# SolderingIronDriver-V1_5-PTH.net
KiCad netlist of a schematic drawn in EAGLE
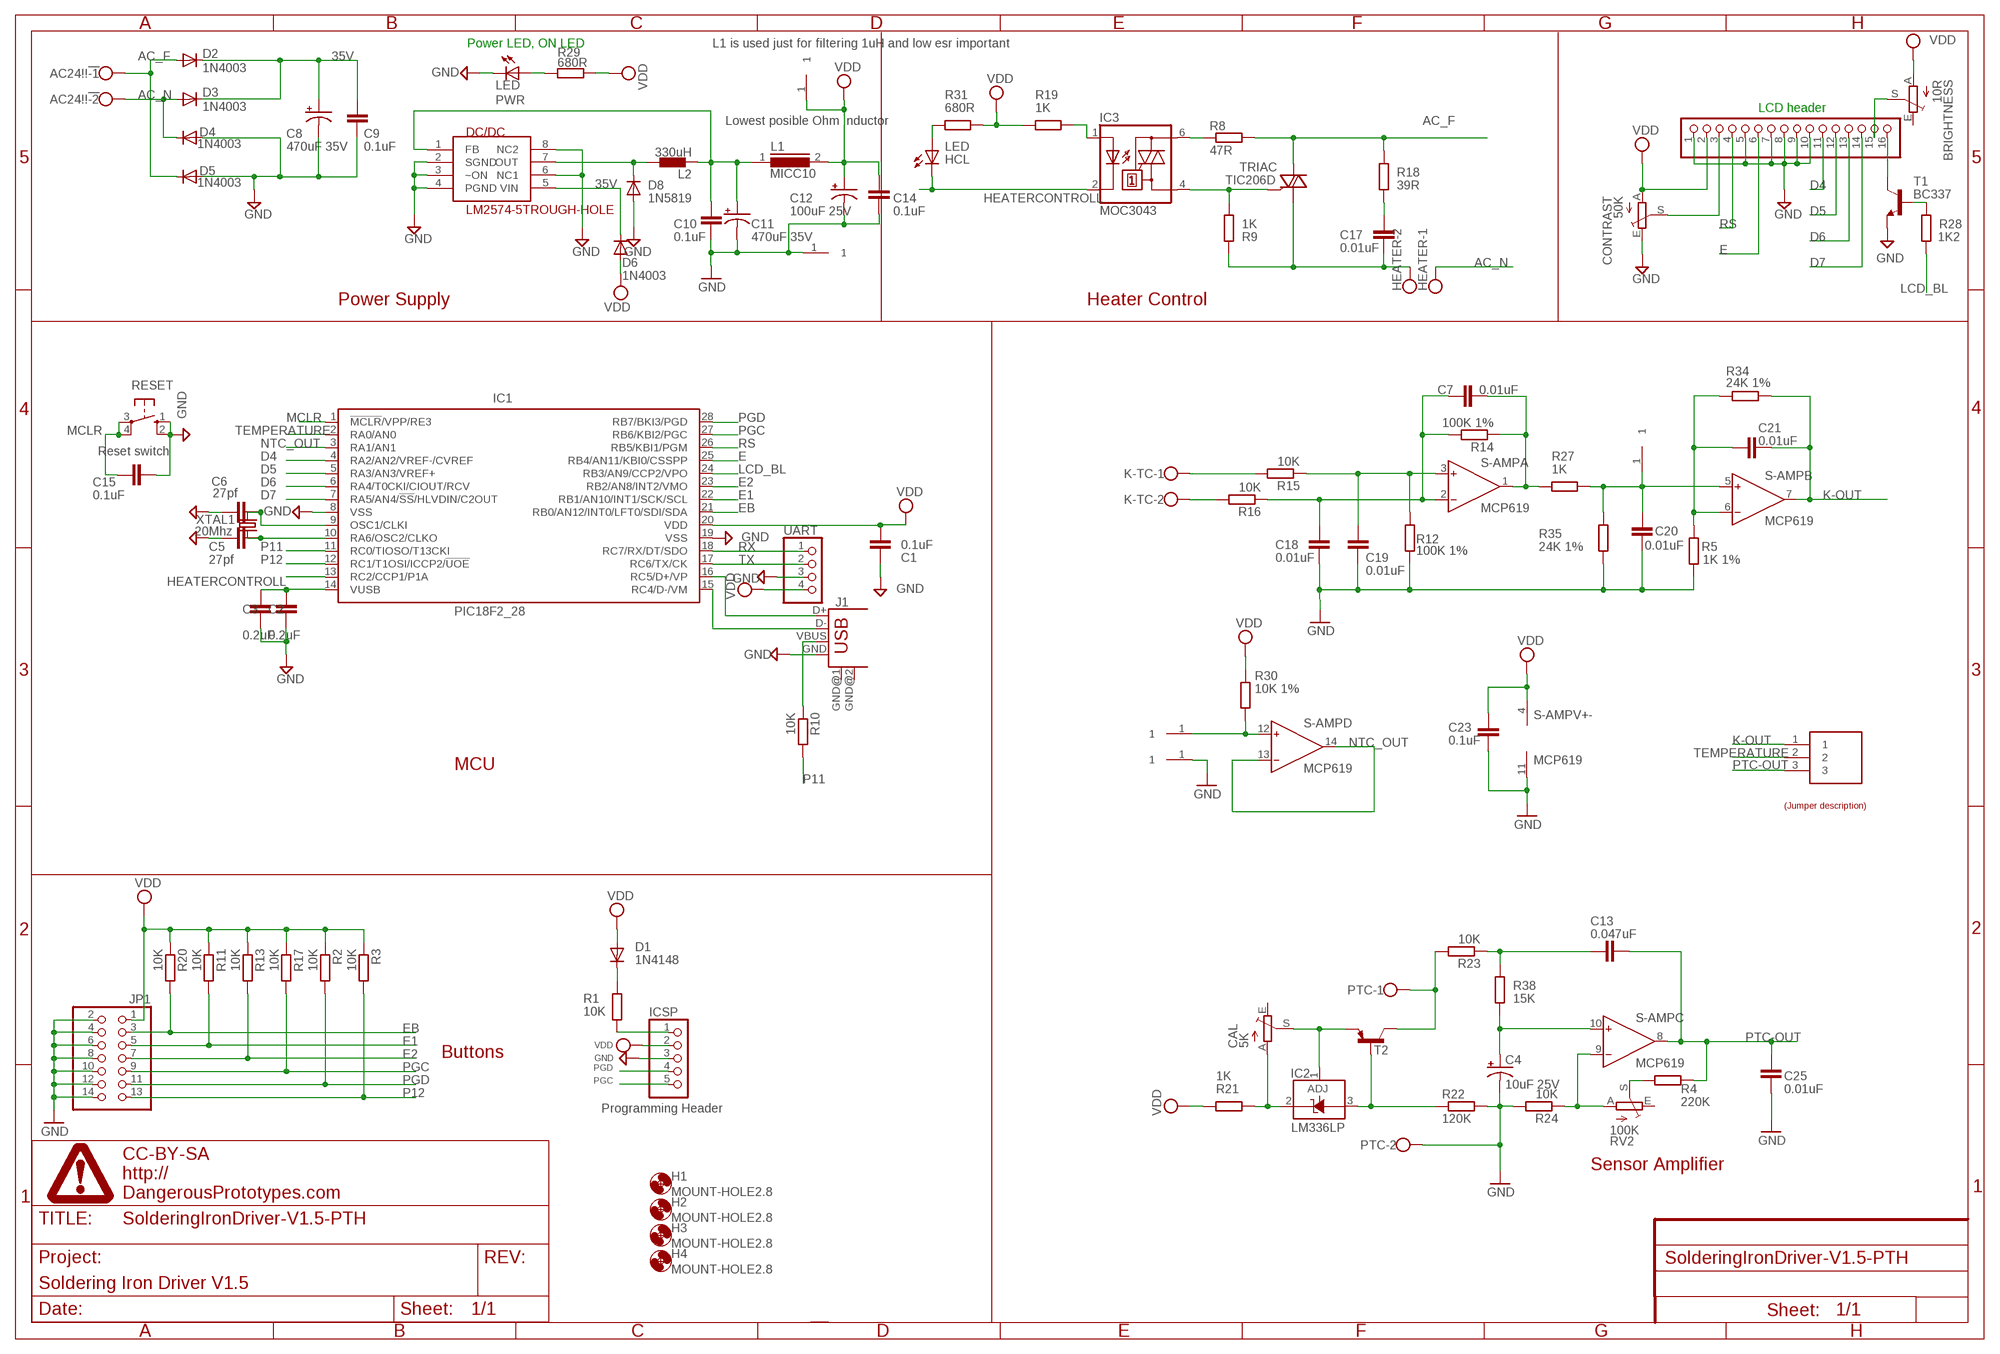
[diagram p0: schematic, sheet 1]

(export (version "E")
  (design (tool "Eeschema 10.0.6"))
  (components
    (comp (ref "5V")
      (value "HEADER1X1PTH")
      (footprint "eagle-import:M1X1")
      (libsource (lib "eagle-import") (part "HEADER1X1PTH"))
    )
    (comp (ref "AC24!!!")
      (value "W237-102")
      (footprint "eagle-import:W237-102")
      (fields (field (name "MPN") "237-102"))
      (libsource (lib "eagle-import") (part "W237-102"))
    )
    (comp (ref "AMP")
      (value "HEADER1X1PTH")
      (footprint "eagle-import:M1X1")
      (libsource (lib "eagle-import") (part "HEADER1X1PTH"))
    )
    (comp (ref "BRIGHTNESS")
      (value "10R")
      (footprint "eagle-import:B25P")
      (libsource (lib "eagle-import") (part "pot_TRIM_EU-B25P"))
    )
    (comp (ref "C1")
      (value "0.1uF")
      (footprint "eagle-import:DEC")
      (libsource (lib "eagle-import") (part "CAPDECOUPLING"))
    )
    (comp (ref "C2")
      (value "0.2uF")
      (footprint "eagle-import:DEC")
      (libsource (lib "eagle-import") (part "CAPDECOUPLING"))
    )
    (comp (ref "C3")
      (value "0.2uF")
      (footprint "eagle-import:DEC")
      (libsource (lib "eagle-import") (part "CAPDECOUPLING"))
    )
    (comp (ref "C4")
      (value "10uF 25V")
      (footprint "eagle-import:CPOL-RADIAL-10UF-25V")
      (libsource (lib "eagle-import") (part "CAP_POLPTH2"))
    )
    (comp (ref "C5")
      (value "27pf")
      (footprint "eagle-import:DEC")
      (libsource (lib "eagle-import") (part "CAPDECOUPLING"))
    )
    (comp (ref "C6")
      (value "27pf")
      (footprint "eagle-import:DEC")
      (libsource (lib "eagle-import") (part "CAPDECOUPLING"))
    )
    (comp (ref "C7")
      (value "0.01uF")
      (footprint "eagle-import:DEC")
      (libsource (lib "eagle-import") (part "CAPDECOUPLING"))
    )
    (comp (ref "C8")
      (value "470uF 35V")
      (footprint "eagle-import:CAP-D10-P200MIL")
      (libsource (lib "eagle-import") (part "CAP-ELD10-P200"))
    )
    (comp (ref "C9")
      (value "0.1uF")
      (footprint "eagle-import:DEC")
      (libsource (lib "eagle-import") (part "CAPDECOUPLING"))
    )
    (comp (ref "C10")
      (value "0.1uF")
      (footprint "eagle-import:DEC")
      (libsource (lib "eagle-import") (part "CAPDECOUPLING"))
    )
    (comp (ref "C11")
      (value "470uF 35V")
      (footprint "eagle-import:CAP-D6.3MM-P100MIL")
      (libsource (lib "eagle-import") (part "CAP-ELD63MP100"))
    )
    (comp (ref "C12")
      (value "100uF 25V")
      (footprint "eagle-import:CPOL-RADIAL-100UF-25V")
      (libsource (lib "eagle-import") (part "CAP_POLPTH1"))
    )
    (comp (ref "C13")
      (value "0.047uF")
      (footprint "eagle-import:DEC")
      (libsource (lib "eagle-import") (part "CAPDECOUPLING"))
    )
    (comp (ref "C14")
      (value "0.1uF")
      (footprint "eagle-import:DEC")
      (libsource (lib "eagle-import") (part "CAPDECOUPLING"))
    )
    (comp (ref "C15")
      (value "0.1uF")
      (footprint "eagle-import:DEC")
      (libsource (lib "eagle-import") (part "CAPDECOUPLING"))
    )
    (comp (ref "C17")
      (value "0.01uF")
      (footprint "eagle-import:DEC")
      (libsource (lib "eagle-import") (part "CAPDECOUPLING"))
    )
    (comp (ref "C18")
      (value "0.01uF")
      (footprint "eagle-import:DEC")
      (libsource (lib "eagle-import") (part "CAPDECOUPLING"))
    )
    (comp (ref "C19")
      (value "0.01uF")
      (footprint "eagle-import:DEC")
      (libsource (lib "eagle-import") (part "CAPDECOUPLING"))
    )
    (comp (ref "C20")
      (value "0.01uF")
      (footprint "eagle-import:DEC")
      (libsource (lib "eagle-import") (part "CAPDECOUPLING"))
    )
    (comp (ref "C21")
      (value "0.01uF")
      (footprint "eagle-import:DEC")
      (libsource (lib "eagle-import") (part "CAPDECOUPLING"))
    )
    (comp (ref "C23")
      (value "0.1uF")
      (footprint "eagle-import:DEC")
      (libsource (lib "eagle-import") (part "CAPDECOUPLING"))
    )
    (comp (ref "C25")
      (value "0.01uF")
      (footprint "eagle-import:DEC")
      (libsource (lib "eagle-import") (part "CAPDECOUPLING"))
    )
    (comp (ref "CAL")
      (value "5K")
      (footprint "eagle-import:RJ9W")
      (libsource (lib "eagle-import") (part "TRIM_EU-RJ9W"))
    )
    (comp (ref "CONTRAST")
      (value "50K")
      (footprint "eagle-import:B25P")
      (libsource (lib "eagle-import") (part "pot_TRIM_EU-B25P"))
    )
    (comp (ref "D1")
      (value "1N4148")
      (footprint "eagle-import:DO35-7")
      (libsource (lib "eagle-import") (part "1N4148DO35-7"))
    )
    (comp (ref "D2")
      (value "1N4003")
      (footprint "eagle-import:DO41-7.6")
      (libsource (lib "eagle-import") (part "DIODE-DO41-7.6"))
    )
    (comp (ref "D3")
      (value "1N4003")
      (footprint "eagle-import:DO41-7.6")
      (libsource (lib "eagle-import") (part "DIODE-DO41-7.6"))
    )
    (comp (ref "D4")
      (value "1N4003")
      (footprint "eagle-import:DO41-7.6")
      (libsource (lib "eagle-import") (part "DIODE-DO41-7.6"))
    )
    (comp (ref "D5")
      (value "1N4003")
      (footprint "eagle-import:DO41-7.6")
      (libsource (lib "eagle-import") (part "DIODE-DO41-7.6"))
    )
    (comp (ref "D6")
      (value "1N4003")
      (footprint "eagle-import:DO41-7.6")
      (libsource (lib "eagle-import") (part "DIODE-DO41-7.6"))
    )
    (comp (ref "D8")
      (value "1N5819")
      (footprint "eagle-import:DO41-7.6")
      (libsource (lib "eagle-import") (part "DIODE-DO41-7.6"))
    )
    (comp (ref "DC/DC")
      (value "LM2574-5TROUGH-HOLE")
      (footprint "eagle-import:DIL-08")
      (libsource (lib "eagle-import") (part "LM2574-5TROUGH-HOLE"))
    )
    (comp (ref "GND")
      (value "HEADER1X1PTH")
      (footprint "eagle-import:M1X1")
      (libsource (lib "eagle-import") (part "HEADER1X1PTH"))
    )
    (comp (ref "H1")
      (value "MOUNT-HOLE2.8")
      (footprint "eagle-import:2,8")
      (libsource (lib "eagle-import") (part "MOUNT-HOLE2.8"))
    )
    (comp (ref "H2")
      (value "MOUNT-HOLE2.8")
      (footprint "eagle-import:2,8")
      (libsource (lib "eagle-import") (part "MOUNT-HOLE2.8"))
    )
    (comp (ref "H3")
      (value "MOUNT-HOLE2.8")
      (footprint "eagle-import:2,8")
      (libsource (lib "eagle-import") (part "MOUNT-HOLE2.8"))
    )
    (comp (ref "H4")
      (value "MOUNT-HOLE2.8")
      (footprint "eagle-import:2,8")
      (libsource (lib "eagle-import") (part "MOUNT-HOLE2.8"))
    )
    (comp (ref "HCL")
      (value "LED")
      (footprint "eagle-import:LED3MM")
      (libsource (lib "eagle-import") (part "LED3MM"))
    )
    (comp (ref "HEATER")
      (value "W237-102")
      (footprint "eagle-import:W237-102")
      (fields (field (name "MPN") "237-102"))
      (libsource (lib "eagle-import") (part "W237-102"))
    )
    (comp (ref "IC1")
      (value "PIC18F2_28")
      (footprint "eagle-import:SOCKET-28-3")
      (libsource (lib "eagle-import") (part "PIC18F2_28"))
    )
    (comp (ref "IC2")
      (value "LM336LP")
      (footprint "eagle-import:TO92")
      (libsource (lib "eagle-import") (part "LM336LP"))
    )
    (comp (ref "IC3")
      (value "MOC3043")
      (footprint "eagle-import:DIL06")
      (fields (field (name "MF") "FAIRCHILD SEMICONDUCTOR") (field (name "MPN") "MOC3043-M"))
      (libsource (lib "eagle-import") (part "MOC3043M"))
    )
    (comp (ref "ICSP")
      (value "PINHD-1X5")
      (footprint "eagle-import:1X05")
      (libsource (lib "eagle-import") (part "PINHD-1X5"))
    )
    (comp (ref "JP1")
      (value "PINHD-2X7")
      (footprint "eagle-import:2X07")
      (libsource (lib "eagle-import") (part "PINHD-2X7"))
    )
    (comp (ref "K-TC")
      (value "W237-102")
      (footprint "eagle-import:W237-102")
      (fields (field (name "MPN") "237-102"))
      (libsource (lib "eagle-import") (part "W237-102"))
    )
    (comp (ref "L1")
      (value "MICC10")
      (footprint "eagle-import:MICC10")
      (libsource (lib "eagle-import") (part "MICC10"))
    )
    (comp (ref "L2")
      (value "330uH")
      (footprint "eagle-import:CW8A")
      (libsource (lib "eagle-import") (part "CL330UH"))
    )
    (comp (ref "LCD_HEADER")
      (value "PINHD-1X16")
      (footprint "eagle-import:1X16")
      (libsource (lib "eagle-import") (part "PINHD-1X16"))
    )
    (comp (ref "NTC")
      (value "HEADER1X1PTH")
      (footprint "eagle-import:M1X1")
      (libsource (lib "eagle-import") (part "HEADER1X1PTH"))
    )
    (comp (ref "ON/OFF2")
      (value "HEADER1X1PTH")
      (footprint "eagle-import:M1X1")
      (libsource (lib "eagle-import") (part "HEADER1X1PTH"))
    )
    (comp (ref "PTC")
      (value "W237-102")
      (footprint "eagle-import:W237-102")
      (fields (field (name "MPN") "237-102"))
      (libsource (lib "eagle-import") (part "W237-102"))
    )
    (comp (ref "PWR")
      (value "LED")
      (footprint "eagle-import:LED3MM")
      (libsource (lib "eagle-import") (part "LED3MM"))
    )
    (comp (ref "R1")
      (value "10K")
      (footprint "eagle-import:0204_7")
      (libsource (lib "eagle-import") (part "R-EU_0204/7"))
    )
    (comp (ref "R2")
      (value "10K")
      (footprint "eagle-import:RTH025W")
      (libsource (lib "eagle-import") (part "RESISTORTH"))
    )
    (comp (ref "R3")
      (value "10K")
      (footprint "eagle-import:RTH025W")
      (libsource (lib "eagle-import") (part "RESISTORTH"))
    )
    (comp (ref "R4")
      (value "220K")
      (footprint "eagle-import:RTH025W")
      (libsource (lib "eagle-import") (part "RESISTORTH"))
    )
    (comp (ref "R5")
      (value "1K 1%")
      (footprint "eagle-import:RTH025W")
      (libsource (lib "eagle-import") (part "RESISTORTH"))
    )
    (comp (ref "R8")
      (value "47R")
      (footprint "eagle-import:RTH025W")
      (libsource (lib "eagle-import") (part "RESISTORTH"))
    )
    (comp (ref "R9")
      (value "1K")
      (footprint "eagle-import:RTH025W")
      (libsource (lib "eagle-import") (part "RESISTORTH"))
    )
    (comp (ref "R10")
      (value "10K")
      (footprint "eagle-import:RTH025W")
      (libsource (lib "eagle-import") (part "RESISTORTH"))
    )
    (comp (ref "R11")
      (value "10K")
      (footprint "eagle-import:RTH025W")
      (libsource (lib "eagle-import") (part "RESISTORTH"))
    )
    (comp (ref "R12")
      (value "100K 1%")
      (footprint "eagle-import:RTH025W")
      (libsource (lib "eagle-import") (part "RESISTORTH"))
    )
    (comp (ref "R13")
      (value "10K")
      (footprint "eagle-import:RTH025W")
      (libsource (lib "eagle-import") (part "RESISTORTH"))
    )
    (comp (ref "R14")
      (value "100K 1%")
      (footprint "eagle-import:RTH025W")
      (libsource (lib "eagle-import") (part "RESISTORTH"))
    )
    (comp (ref "R15")
      (value "10K")
      (footprint "eagle-import:RTH025W")
      (libsource (lib "eagle-import") (part "RESISTORTH"))
    )
    (comp (ref "R16")
      (value "10K")
      (footprint "eagle-import:RTH025W")
      (libsource (lib "eagle-import") (part "RESISTORTH"))
    )
    (comp (ref "R17")
      (value "10K")
      (footprint "eagle-import:RTH025W")
      (libsource (lib "eagle-import") (part "RESISTORTH"))
    )
    (comp (ref "R18")
      (value "39R")
      (footprint "eagle-import:RTH025W")
      (libsource (lib "eagle-import") (part "RESISTORTH"))
    )
    (comp (ref "R19")
      (value "1K")
      (footprint "eagle-import:RTH025W")
      (libsource (lib "eagle-import") (part "RESISTORTH"))
    )
    (comp (ref "R20")
      (value "10K")
      (footprint "eagle-import:RTH025W")
      (libsource (lib "eagle-import") (part "RESISTORTH"))
    )
    (comp (ref "R21")
      (value "1K")
      (footprint "eagle-import:RTH025W")
      (libsource (lib "eagle-import") (part "RESISTORTH"))
    )
    (comp (ref "R22")
      (value "120K")
      (footprint "eagle-import:RTH025W")
      (libsource (lib "eagle-import") (part "RESISTORTH"))
    )
    (comp (ref "R23")
      (value "10K")
      (footprint "eagle-import:RTH025W")
      (libsource (lib "eagle-import") (part "RESISTORTH"))
    )
    (comp (ref "R24")
      (value "10K")
      (footprint "eagle-import:RTH025W")
      (libsource (lib "eagle-import") (part "RESISTORTH"))
    )
    (comp (ref "R27")
      (value "1K")
      (footprint "eagle-import:RTH025W")
      (libsource (lib "eagle-import") (part "RESISTORTH"))
    )
    (comp (ref "R28")
      (value "1K2")
      (footprint "eagle-import:RTH025W")
      (libsource (lib "eagle-import") (part "RESISTORTH"))
    )
    (comp (ref "R29")
      (value "680R")
      (footprint "eagle-import:RTH025W")
      (libsource (lib "eagle-import") (part "RESISTORTH"))
    )
    (comp (ref "R30")
      (value "10K 1%")
      (footprint "eagle-import:RTH025W")
      (libsource (lib "eagle-import") (part "RESISTORTH"))
    )
    (comp (ref "R31")
      (value "680R")
      (footprint "eagle-import:RTH025W")
      (libsource (lib "eagle-import") (part "RESISTORTH"))
    )
    (comp (ref "R34")
      (value "24K 1%")
      (footprint "eagle-import:RTH025W")
      (libsource (lib "eagle-import") (part "RESISTORTH"))
    )
    (comp (ref "R35")
      (value "24K 1%")
      (footprint "eagle-import:RTH025W")
      (libsource (lib "eagle-import") (part "RESISTORTH"))
    )
    (comp (ref "R38")
      (value "15K")
      (footprint "eagle-import:RTH025W")
      (libsource (lib "eagle-import") (part "RESISTORTH"))
    )
    (comp (ref "RESET")
      (value "10-XX")
      (footprint "eagle-import:B3F-10XX")
      (fields (field (name "MPN") "B3F-1000"))
      (libsource (lib "eagle-import") (part "10-XX"))
    )
    (comp (ref "RV2")
      (value "100K")
      (footprint "eagle-import:RJ9W")
      (libsource (lib "eagle-import") (part "TRIM_EU-RJ9W"))
    )
    (comp (ref "S-AMP")
      (value "MCP619")
      (footprint "eagle-import:SOCKET-14")
      (libsource (lib "eagle-import") (part "MCP619"))
    )
    (comp (ref "SENSOR_SELECT")
      (value "HEADER1X3PTH")
      (footprint "eagle-import:M1X3")
      (libsource (lib "eagle-import") (part "HEADER1X3PTH"))
    )
    (comp (ref "T1")
      (value "BC337")
      (footprint "eagle-import:TO92-CBE")
      (libsource (lib "eagle-import") (part "-NPN-TO92-CBEBC337-40"))
    )
    (comp (ref "T2")
      (value "BJT-PNPTO92EBC")
      (footprint "eagle-import:TO92-EBC")
      (libsource (lib "eagle-import") (part "BJT-PNPTO92EBC"))
    )
    (comp (ref "TRIAC")
      (value "TIC206D")
      (footprint "eagle-import:TO220BV")
      (libsource (lib "eagle-import") (part "TIC206D"))
    )
    (comp (ref "U$1")
      (value "DINA4_L")
      (footprint "eagle-import:DP_LOGO")
      (fields (field (name "PROJECT") "Soldering Iron Driver V1.5"))
      (libsource (lib "eagle-import") (part "DINA4_L"))
    )
    (comp (ref "U$2")
      (value "JUMP3_DESC")
      (footprint "eagle-import:JUMP3_DESC")
      (fields (field (name "LEFT") "PTC") (field (name "RIGHT") "K-TC"))
      (libsource (lib "eagle-import") (part "JUMP3_DESC"))
    )
    (comp (ref "UART")
      (value "PINHD-1X4")
      (footprint "eagle-import:1X04")
      (libsource (lib "eagle-import") (part "PINHD-1X4"))
    )
    (comp (ref "USB")
      (value "USB")
      (footprint "eagle-import:USB-B-H")
      (libsource (lib "eagle-import") (part "USB-B-H"))
    )
    (comp (ref "XTAL1")
      (value "20Mhz")
      (footprint "eagle-import:HC49U70")
      (libsource (lib "eagle-import") (part "CRYSTALHC49U70"))
    )
  )
  (nets
    (net (code "1") (name "/35V") (class "Default")
      (node (ref "C8") (pin "+") (pinfunction "+_+") (pintype "passive"))
      (node (ref "C9") (pin "2") (pinfunction "2_2") (pintype "passive"))
      (node (ref "D2") (pin "C") (pinfunction "C_C") (pintype "passive"))
      (node (ref "D3") (pin "C") (pinfunction "C_C") (pintype "passive"))
      (node (ref "D6") (pin "C") (pinfunction "C_C") (pintype "passive"))
      (node (ref "DC/DC") (pin "5") (pinfunction "VIN_5") (pintype "bidirectional"))
    )
    (net (code "2") (name "/AC_F") (class "Default")
      (node (ref "AC24!!!") (pin "1") (pinfunction "KL_1") (pintype "passive"))
      (node (ref "D2") (pin "A") (pinfunction "A_A") (pintype "passive"))
      (node (ref "D5") (pin "C") (pinfunction "C_C") (pintype "passive"))
      (node (ref "R18") (pin "1") (pinfunction "1_1") (pintype "passive"))
      (node (ref "R8") (pin "2") (pinfunction "2_2") (pintype "passive"))
      (node (ref "TRIAC") (pin "T2") (pinfunction "A2_T2") (pintype "passive"))
    )
    (net (code "3") (name "/AC_N") (class "Default")
      (node (ref "AC24!!!") (pin "2") (pinfunction "KL_2") (pintype "passive"))
      (node (ref "D3") (pin "A") (pinfunction "A_A") (pintype "passive"))
      (node (ref "D4") (pin "C") (pinfunction "C_C") (pintype "passive"))
      (node (ref "HEATER") (pin "1") (pinfunction "KL_1") (pintype "passive"))
    )
    (net (code "4") (name "/D4") (class "Default")
      (node (ref "IC1") (pin "4") (pinfunction "RA2/AN2/VREF-/CVREF_4") (pintype "bidirectional"))
      (node (ref "LCD_HEADER") (pin "11") (pinfunction "11_11") (pintype "passive"))
    )
    (net (code "5") (name "/D5") (class "Default")
      (node (ref "IC1") (pin "5") (pinfunction "RA3/AN3/VREF+_5") (pintype "bidirectional"))
      (node (ref "LCD_HEADER") (pin "12") (pinfunction "12_12") (pintype "passive"))
    )
    (net (code "6") (name "/D6") (class "Default")
      (node (ref "IC1") (pin "6") (pinfunction "RA4/T0CKI/CIOUT/RCV_6") (pintype "bidirectional"))
      (node (ref "LCD_HEADER") (pin "13") (pinfunction "13_13") (pintype "passive"))
    )
    (net (code "7") (name "/D7") (class "Default")
      (node (ref "IC1") (pin "7") (pinfunction "RA5/AN4/~{SS}/HLVDIN/C2OUT_7") (pintype "bidirectional"))
      (node (ref "LCD_HEADER") (pin "14") (pinfunction "14_14") (pintype "passive"))
    )
    (net (code "8") (name "/E") (class "Default")
      (node (ref "IC1") (pin "25") (pinfunction "RB4/AN11/KBI0/CSSPP_25") (pintype "bidirectional"))
      (node (ref "LCD_HEADER") (pin "6") (pinfunction "6_6") (pintype "passive"))
    )
    (net (code "9") (name "/E1") (class "Default")
      (node (ref "IC1") (pin "22") (pinfunction "RB1/AN10/INT1/SCK/SCL_22") (pintype "bidirectional"))
      (node (ref "JP1") (pin "5") (pinfunction "5_5") (pintype "passive"))
      (node (ref "R11") (pin "2") (pinfunction "2_2") (pintype "passive"))
    )
    (net (code "10") (name "/E2") (class "Default")
      (node (ref "IC1") (pin "23") (pinfunction "RB2/AN8/INT2/VMO_23") (pintype "bidirectional"))
      (node (ref "JP1") (pin "7") (pinfunction "7_7") (pintype "passive"))
      (node (ref "R13") (pin "2") (pinfunction "2_2") (pintype "passive"))
    )
    (net (code "11") (name "/EB") (class "Default")
      (node (ref "IC1") (pin "21") (pinfunction "RB0/AN12/INT0/LFT0/SDI/SDA_21") (pintype "bidirectional"))
      (node (ref "JP1") (pin "3") (pinfunction "3_3") (pintype "passive"))
      (node (ref "R20") (pin "2") (pinfunction "2_2") (pintype "passive"))
    )
    (net (code "12") (name "/HEATERCONTROLL") (class "Default")
      (node (ref "HCL") (pin "K") (pinfunction "C_K") (pintype "passive"))
      (node (ref "IC1") (pin "13") (pinfunction "RC2/CCP1/P1A_13") (pintype "bidirectional"))
      (node (ref "IC3") (pin "2") (pinfunction "C_2") (pintype "passive"))
    )
    (net (code "13") (name "/K-OUT") (class "Default")
      (node (ref "C21") (pin "2") (pinfunction "2_2") (pintype "passive"))
      (node (ref "R34") (pin "2") (pinfunction "2_2") (pintype "passive"))
      (node (ref "S-AMP") (pin "7") (pinfunction "OUT_7") (pintype "output"))
      (node (ref "SENSOR_SELECT") (pin "1") (pinfunction "1_1") (pintype "bidirectional"))
    )
    (net (code "14") (name "/LCD_BL") (class "Default")
      (node (ref "IC1") (pin "24") (pinfunction "RB3/AN9/CCP2/VPO_24") (pintype "bidirectional"))
      (node (ref "R28") (pin "2") (pinfunction "2_2") (pintype "passive"))
    )
    (net (code "15") (name "/MCLR") (class "Default")
      (node (ref "C15") (pin "2") (pinfunction "2_2") (pintype "passive"))
      (node (ref "IC1") (pin "1") (pinfunction "~{MCLR}/VPP/RE3_1") (pintype "input"))
      (node (ref "ICSP") (pin "1") (pinfunction "1_1") (pintype "passive"))
      (node (ref "R1") (pin "1") (pinfunction "1_1") (pintype "passive"))
      (node (ref "RESET") (pin "3") (pinfunction "P_3") (pintype "passive"))
      (node (ref "RESET") (pin "4") (pinfunction "P1_4") (pintype "passive"))
    )
    (net (code "16") (name "/NTC_OUT") (class "Default")
      (node (ref "IC1") (pin "3") (pinfunction "RA1/AN1_3") (pintype "bidirectional"))
      (node (ref "S-AMP") (pin "13") (pinfunction "IN-_13") (pintype "input"))
      (node (ref "S-AMP") (pin "14") (pinfunction "OUT_14") (pintype "output"))
    )
    (net (code "17") (name "/P11") (class "Default")
      (node (ref "IC1") (pin "11") (pinfunction "RC0/TIOSO/T13CKI_11") (pintype "bidirectional"))
      (node (ref "R10") (pin "2") (pinfunction "2_2") (pintype "passive"))
    )
    (net (code "18") (name "/P12") (class "Default")
      (node (ref "IC1") (pin "12") (pinfunction "RC1/T1OSI/ICCP2/~{UOE}_12") (pintype "bidirectional"))
      (node (ref "JP1") (pin "13") (pinfunction "13_13") (pintype "passive"))
      (node (ref "R3") (pin "2") (pinfunction "2_2") (pintype "passive"))
    )
    (net (code "19") (name "/PGC") (class "Default")
      (node (ref "IC1") (pin "27") (pinfunction "RB6/KBI2/PGC_27") (pintype "bidirectional"))
      (node (ref "ICSP") (pin "5") (pinfunction "5_5") (pintype "passive"))
      (node (ref "JP1") (pin "9") (pinfunction "9_9") (pintype "passive"))
      (node (ref "R17") (pin "2") (pinfunction "2_2") (pintype "passive"))
    )
    (net (code "20") (name "/PGD") (class "Default")
      (node (ref "IC1") (pin "28") (pinfunction "RB7/BKI3/PGD_28") (pintype "bidirectional"))
      (node (ref "ICSP") (pin "4") (pinfunction "4_4") (pintype "passive"))
      (node (ref "JP1") (pin "11") (pinfunction "11_11") (pintype "passive"))
      (node (ref "R2") (pin "2") (pinfunction "2_2") (pintype "passive"))
    )
    (net (code "21") (name "/PTC-OUT") (class "Default")
      (node (ref "C13") (pin "2") (pinfunction "2_2") (pintype "passive"))
      (node (ref "C25") (pin "2") (pinfunction "2_2") (pintype "passive"))
      (node (ref "R4") (pin "1") (pinfunction "1_1") (pintype "passive"))
      (node (ref "S-AMP") (pin "8") (pinfunction "OUT_8") (pintype "output"))
      (node (ref "SENSOR_SELECT") (pin "3") (pinfunction "3_3") (pintype "bidirectional"))
    )
    (net (code "22") (name "/RS") (class "Default")
      (node (ref "IC1") (pin "26") (pinfunction "RB5/KBI1/PGM_26") (pintype "bidirectional"))
      (node (ref "LCD_HEADER") (pin "4") (pinfunction "4_4") (pintype "passive"))
    )
    (net (code "23") (name "/RX") (class "Default")
      (node (ref "IC1") (pin "18") (pinfunction "RC7/RX/DT/SDO_18") (pintype "bidirectional"))
      (node (ref "UART") (pin "1") (pinfunction "1_1") (pintype "passive"))
    )
    (net (code "24") (name "/TEMPERATURE") (class "Default")
      (node (ref "IC1") (pin "2") (pinfunction "RA0/AN0_2") (pintype "bidirectional"))
      (node (ref "SENSOR_SELECT") (pin "2") (pinfunction "2_2") (pintype "bidirectional"))
    )
    (net (code "25") (name "/TX") (class "Default")
      (node (ref "IC1") (pin "17") (pinfunction "RC6/TX/CK_17") (pintype "bidirectional"))
      (node (ref "UART") (pin "2") (pinfunction "2_2") (pintype "passive"))
    )
    (net (code "26") (name "GND") (class "Default")
      (node (ref "C1") (pin "2") (pinfunction "2_2") (pintype "passive"))
      (node (ref "C10") (pin "1") (pinfunction "1_1") (pintype "passive"))
      (node (ref "C11") (pin "-") (pinfunction "-_-") (pintype "passive"))
      (node (ref "C12") (pin "2") (pinfunction "-_2") (pintype "passive"))
      (node (ref "C14") (pin "1") (pinfunction "1_1") (pintype "passive"))
      (node (ref "C15") (pin "1") (pinfunction "1_1") (pintype "passive"))
      (node (ref "C18") (pin "2") (pinfunction "2_2") (pintype "passive"))
      (node (ref "C19") (pin "2") (pinfunction "2_2") (pintype "passive"))
      (node (ref "C2") (pin "2") (pinfunction "2_2") (pintype "passive"))
      (node (ref "C20") (pin "2") (pinfunction "2_2") (pintype "passive"))
      (node (ref "C23") (pin "1") (pinfunction "1_1") (pintype "passive"))
      (node (ref "C25") (pin "1") (pinfunction "1_1") (pintype "passive"))
      (node (ref "C3") (pin "2") (pinfunction "2_2") (pintype "passive"))
      (node (ref "C4") (pin "2") (pinfunction "-_2") (pintype "passive"))
      (node (ref "C5") (pin "2") (pinfunction "2_2") (pintype "passive"))
      (node (ref "C6") (pin "2") (pinfunction "2_2") (pintype "passive"))
      (node (ref "C8") (pin "-") (pinfunction "-_-") (pintype "passive"))
      (node (ref "C9") (pin "1") (pinfunction "1_1") (pintype "passive"))
      (node (ref "CONTRAST") (pin "E") (pinfunction "E_E") (pintype "passive"))
      (node (ref "D4") (pin "A") (pinfunction "A_A") (pintype "passive"))
      (node (ref "D5") (pin "A") (pinfunction "A_A") (pintype "passive"))
      (node (ref "D8") (pin "A") (pinfunction "A_A") (pintype "passive"))
      (node (ref "DC/DC") (pin "2") (pinfunction "SGND_2") (pintype "bidirectional"))
      (node (ref "DC/DC") (pin "3") (pinfunction "~{ON}_3") (pintype "bidirectional"))
      (node (ref "DC/DC") (pin "4") (pinfunction "PGND_4") (pintype "bidirectional"))
      (node (ref "DC/DC") (pin "6") (pinfunction "NC1_6") (pintype "bidirectional"))
      (node (ref "DC/DC") (pin "8") (pinfunction "NC2_8") (pintype "bidirectional"))
      (node (ref "GND") (pin "1") (pinfunction "1_1") (pintype "bidirectional"))
      (node (ref "IC1") (pin "19") (pinfunction "VSS_19") (pintype "power_in"))
      (node (ref "IC1") (pin "8") (pinfunction "VSS_8") (pintype "power_in"))
      (node (ref "ICSP") (pin "3") (pinfunction "3_3") (pintype "passive"))
      (node (ref "JP1") (pin "10") (pinfunction "10_10") (pintype "passive"))
      (node (ref "JP1") (pin "12") (pinfunction "12_12") (pintype "passive"))
      (node (ref "JP1") (pin "14") (pinfunction "14_14") (pintype "passive"))
      (node (ref "JP1") (pin "2") (pinfunction "2_2") (pintype "passive"))
      (node (ref "JP1") (pin "4") (pinfunction "4_4") (pintype "passive"))
      (node (ref "JP1") (pin "6") (pinfunction "6_6") (pintype "passive"))
      (node (ref "JP1") (pin "8") (pinfunction "8_8") (pintype "passive"))
      (node (ref "LCD_HEADER") (pin "1") (pinfunction "1_1") (pintype "passive"))
      (node (ref "LCD_HEADER") (pin "10") (pinfunction "10_10") (pintype "passive"))
      (node (ref "LCD_HEADER") (pin "5") (pinfunction "5_5") (pintype "passive"))
      (node (ref "LCD_HEADER") (pin "7") (pinfunction "7_7") (pintype "passive"))
      (node (ref "LCD_HEADER") (pin "8") (pinfunction "8_8") (pintype "passive"))
      (node (ref "LCD_HEADER") (pin "9") (pinfunction "9_9") (pintype "passive"))
      (node (ref "ON/OFF2") (pin "1") (pinfunction "1_1") (pintype "bidirectional"))
      (node (ref "PTC") (pin "2") (pinfunction "KL_2") (pintype "passive"))
      (node (ref "PWR") (pin "K") (pinfunction "C_K") (pintype "passive"))
      (node (ref "R12") (pin "1") (pinfunction "1_1") (pintype "passive"))
      (node (ref "R22") (pin "2") (pinfunction "2_2") (pintype "passive"))
      (node (ref "R24") (pin "2") (pinfunction "2_2") (pintype "passive"))
      (node (ref "R35") (pin "1") (pinfunction "1_1") (pintype "passive"))
      (node (ref "R5") (pin "1") (pinfunction "1_1") (pintype "passive"))
      (node (ref "RESET") (pin "1") (pinfunction "S_1") (pintype "passive"))
      (node (ref "RESET") (pin "2") (pinfunction "S1_2") (pintype "passive"))
      (node (ref "S-AMP") (pin "11") (pinfunction "V-_11") (pintype "power_in"))
      (node (ref "T1") (pin "E") (pinfunction "E_E") (pintype "passive"))
      (node (ref "UART") (pin "3") (pinfunction "3_3") (pintype "passive"))
      (node (ref "USB") (pin "GND") (pinfunction "GND_GND") (pintype "bidirectional"))
    )
    (net (code "27") (name "Net-(BRIGHTNESS-PadS)") (class "Default")
      (node (ref "BRIGHTNESS") (pin "S") (pinfunction "S_S") (pintype "passive"))
      (node (ref "LCD_HEADER") (pin "15") (pinfunction "15_15") (pintype "passive"))
    )
    (net (code "28") (name "Net-(C4-+)") (class "Default")
      (node (ref "C4") (pin "1") (pinfunction "+_1") (pintype "passive"))
      (node (ref "R38") (pin "1") (pinfunction "1_1") (pintype "passive"))
      (node (ref "S-AMP") (pin "10") (pinfunction "IN+_10") (pintype "input"))
    )
    (net (code "29") (name "Net-(C13-Pad1)") (class "Default")
      (node (ref "C13") (pin "1") (pinfunction "1_1") (pintype "passive"))
      (node (ref "R23") (pin "1") (pinfunction "1_1") (pintype "passive"))
      (node (ref "R38") (pin "2") (pinfunction "2_2") (pintype "passive"))
    )
    (net (code "30") (name "Net-(C17-Pad1)") (class "Default")
      (node (ref "C17") (pin "1") (pinfunction "1_1") (pintype "passive"))
      (node (ref "R18") (pin "2") (pinfunction "2_2") (pintype "passive"))
    )
    (net (code "31") (name "Net-(CONTRAST-PadS)") (class "Default")
      (node (ref "CONTRAST") (pin "S") (pinfunction "S_S") (pintype "passive"))
      (node (ref "LCD_HEADER") (pin "3") (pinfunction "3_3") (pintype "passive"))
    )
    (net (code "32") (name "Net-(D1-PadC)") (class "Default")
      (node (ref "D1") (pin "C") (pinfunction "C_C") (pintype "passive"))
      (node (ref "R1") (pin "2") (pinfunction "2_2") (pintype "passive"))
    )
    (net (code "33") (name "Net-(DC/DC-FB)") (class "Default")
      (node (ref "C10") (pin "2") (pinfunction "2_2") (pintype "passive"))
      (node (ref "C11") (pin "+") (pinfunction "+_+") (pintype "passive"))
      (node (ref "DC/DC") (pin "1") (pinfunction "FB_1") (pintype "bidirectional"))
      (node (ref "L1") (pin "1") (pinfunction "1_1") (pintype "passive"))
      (node (ref "L2") (pin "1") (pinfunction "1_1") (pintype "passive"))
    )
    (net (code "34") (name "Net-(DC/DC-OUT)") (class "Default")
      (node (ref "D8") (pin "C") (pinfunction "C_C") (pintype "passive"))
      (node (ref "DC/DC") (pin "7") (pinfunction "OUT_7") (pintype "bidirectional"))
      (node (ref "L2") (pin "2") (pinfunction "2_2") (pintype "passive"))
    )
    (net (code "35") (name "Net-(HCL-PadA)") (class "Default")
      (node (ref "HCL") (pin "A") (pinfunction "A_A") (pintype "passive"))
      (node (ref "R31") (pin "1") (pinfunction "1_1") (pintype "passive"))
    )
    (net (code "36") (name "Net-(HEATERB-KL)") (class "Default")
      (node (ref "C17") (pin "2") (pinfunction "2_2") (pintype "passive"))
      (node (ref "HEATER") (pin "2") (pinfunction "KL_2") (pintype "passive"))
      (node (ref "R9") (pin "2") (pinfunction "2_2") (pintype "passive"))
      (node (ref "TRIAC") (pin "T1") (pinfunction "A1_T1") (pintype "passive"))
    )
    (net (code "37") (name "Net-(IC1-OSC1{slash}CLKI)") (class "Default")
      (node (ref "C6") (pin "1") (pinfunction "1_1") (pintype "passive"))
      (node (ref "IC1") (pin "9") (pinfunction "OSC1/CLKI_9") (pintype "input"))
      (node (ref "XTAL1") (pin "2") (pinfunction "2_2") (pintype "passive"))
    )
    (net (code "38") (name "Net-(IC1-RA6{slash}OSC2{slash}CLKO)") (class "Default")
      (node (ref "C5") (pin "1") (pinfunction "1_1") (pintype "passive"))
      (node (ref "IC1") (pin "10") (pinfunction "RA6/OSC2/CLKO_10") (pintype "output"))
      (node (ref "XTAL1") (pin "1") (pinfunction "1_1") (pintype "passive"))
    )
    (net (code "39") (name "Net-(IC1-RC4{slash}D-{slash}VM)") (class "Default")
      (node (ref "IC1") (pin "15") (pinfunction "RC4/D-/VM_15") (pintype "bidirectional"))
      (node (ref "USB") (pin "D-") (pinfunction "D-_D-") (pintype "bidirectional"))
    )
    (net (code "40") (name "Net-(IC1-RC5{slash}D+{slash}VP)") (class "Default")
      (node (ref "IC1") (pin "16") (pinfunction "RC5/D+/VP_16") (pintype "bidirectional"))
      (node (ref "USB") (pin "D+") (pinfunction "D+_D+") (pintype "bidirectional"))
    )
    (net (code "41") (name "Net-(IC1-VUSB)") (class "Default")
      (node (ref "C2") (pin "1") (pinfunction "1_1") (pintype "passive"))
      (node (ref "C3") (pin "1") (pinfunction "1_1") (pintype "passive"))
      (node (ref "IC1") (pin "14") (pinfunction "VUSB_14") (pintype "bidirectional"))
    )
    (net (code "42") (name "Net-(IC2-A)") (class "Default")
      (node (ref "IC2") (pin "3") (pinfunction "A_3") (pintype "input"))
      (node (ref "R22") (pin "1") (pinfunction "1_1") (pintype "passive"))
      (node (ref "T2") (pin "B") (pinfunction "B_B") (pintype "passive"))
    )
    (net (code "43") (name "Net-(IC2-ADJ)") (class "Default")
      (node (ref "CAL") (pin "S") (pinfunction "S_S") (pintype "passive"))
      (node (ref "IC2") (pin "1") (pinfunction "ADJ_1") (pintype "input"))
      (node (ref "T2") (pin "E") (pinfunction "E_E") (pintype "passive"))
    )
    (net (code "44") (name "Net-(IC2-C)") (class "Default")
      (node (ref "CAL") (pin "A") (pinfunction "A_A") (pintype "passive"))
      (node (ref "IC2") (pin "2") (pinfunction "C_2") (pintype "passive"))
      (node (ref "R21") (pin "1") (pinfunction "1_1") (pintype "passive"))
    )
    (net (code "45") (name "Net-(IC3-A)") (class "Default")
      (node (ref "IC3") (pin "1") (pinfunction "A_1") (pintype "passive"))
      (node (ref "R19") (pin "2") (pinfunction "2_2") (pintype "passive"))
    )
    (net (code "46") (name "Net-(IC3-A1)") (class "Default")
      (node (ref "IC3") (pin "4") (pinfunction "A1_4") (pintype "passive"))
      (node (ref "R9") (pin "1") (pinfunction "1_1") (pintype "passive"))
      (node (ref "TRIAC") (pin "G") (pinfunction "G_G") (pintype "passive"))
    )
    (net (code "47") (name "Net-(IC3-A2)") (class "Default")
      (node (ref "IC3") (pin "6") (pinfunction "A2_6") (pintype "passive"))
      (node (ref "R8") (pin "1") (pinfunction "1_1") (pintype "passive"))
    )
    (net (code "48") (name "Net-(K-TCA-KL)") (class "Default")
      (node (ref "K-TC") (pin "1") (pinfunction "KL_1") (pintype "passive"))
      (node (ref "R15") (pin "2") (pinfunction "2_2") (pintype "passive"))
    )
    (net (code "49") (name "Net-(K-TCB-KL)") (class "Default")
      (node (ref "K-TC") (pin "2") (pinfunction "KL_2") (pintype "passive"))
      (node (ref "R16") (pin "2") (pinfunction "2_2") (pintype "passive"))
    )
    (net (code "50") (name "Net-(LCD_HEADER-Pad16)") (class "Default")
      (node (ref "LCD_HEADER") (pin "16") (pinfunction "16_16") (pintype "passive"))
      (node (ref "T1") (pin "C") (pinfunction "C_C") (pintype "passive"))
    )
    (net (code "51") (name "Net-(PTCA-KL)") (class "Default")
      (node (ref "PTC") (pin "1") (pinfunction "KL_1") (pintype "passive"))
      (node (ref "R23") (pin "2") (pinfunction "2_2") (pintype "passive"))
      (node (ref "T2") (pin "C") (pinfunction "C_C") (pintype "passive"))
    )
    (net (code "52") (name "Net-(PWR-PadA)") (class "Default")
      (node (ref "PWR") (pin "A") (pinfunction "A_A") (pintype "passive"))
      (node (ref "R29") (pin "1") (pinfunction "1_1") (pintype "passive"))
    )
    (net (code "53") (name "Net-(R4-Pad2)") (class "Default")
      (node (ref "R4") (pin "2") (pinfunction "2_2") (pintype "passive"))
      (node (ref "RV2") (pin "S") (pinfunction "S_S") (pintype "passive"))
    )
    (net (code "54") (name "Net-(R10-Pad1)") (class "Default")
      (node (ref "R10") (pin "1") (pinfunction "1_1") (pintype "passive"))
      (node (ref "USB") (pin "VBUS") (pinfunction "VBUS_VBUS") (pintype "bidirectional"))
    )
    (net (code "55") (name "Net-(R28-Pad1)") (class "Default")
      (node (ref "R28") (pin "1") (pinfunction "1_1") (pintype "passive"))
      (node (ref "T1") (pin "B") (pinfunction "B_B") (pintype "passive"))
    )
    (net (code "56") (name "Net-(S-AMPA-IN+)") (class "Default")
      (node (ref "C19") (pin "1") (pinfunction "1_1") (pintype "passive"))
      (node (ref "R12") (pin "2") (pinfunction "2_2") (pintype "passive"))
      (node (ref "R15") (pin "1") (pinfunction "1_1") (pintype "passive"))
      (node (ref "S-AMP") (pin "3") (pinfunction "IN+_3") (pintype "input"))
    )
    (net (code "57") (name "Net-(S-AMPA-IN-)") (class "Default")
      (node (ref "C18") (pin "1") (pinfunction "1_1") (pintype "passive"))
      (node (ref "C7") (pin "1") (pinfunction "1_1") (pintype "passive"))
      (node (ref "R14") (pin "2") (pinfunction "2_2") (pintype "passive"))
      (node (ref "R16") (pin "1") (pinfunction "1_1") (pintype "passive"))
      (node (ref "S-AMP") (pin "2") (pinfunction "IN-_2") (pintype "input"))
    )
    (net (code "58") (name "Net-(S-AMPA-OUT)") (class "Default")
      (node (ref "C7") (pin "2") (pinfunction "2_2") (pintype "passive"))
      (node (ref "R14") (pin "1") (pinfunction "1_1") (pintype "passive"))
      (node (ref "R27") (pin "2") (pinfunction "2_2") (pintype "passive"))
      (node (ref "S-AMP") (pin "1") (pinfunction "OUT_1") (pintype "output"))
    )
    (net (code "59") (name "Net-(S-AMPB-IN+)") (class "Default")
      (node (ref "AMP") (pin "1") (pinfunction "1_1") (pintype "bidirectional"))
      (node (ref "C20") (pin "1") (pinfunction "1_1") (pintype "passive"))
      (node (ref "R27") (pin "1") (pinfunction "1_1") (pintype "passive"))
      (node (ref "R35") (pin "2") (pinfunction "2_2") (pintype "passive"))
      (node (ref "S-AMP") (pin "5") (pinfunction "IN+_5") (pintype "input"))
    )
    (net (code "60") (name "Net-(S-AMPB-IN-)") (class "Default")
      (node (ref "C21") (pin "1") (pinfunction "1_1") (pintype "passive"))
      (node (ref "R34") (pin "1") (pinfunction "1_1") (pintype "passive"))
      (node (ref "R5") (pin "2") (pinfunction "2_2") (pintype "passive"))
      (node (ref "S-AMP") (pin "6") (pinfunction "IN-_6") (pintype "input"))
    )
    (net (code "61") (name "Net-(S-AMPC-IN-)") (class "Default")
      (node (ref "R24") (pin "1") (pinfunction "1_1") (pintype "passive"))
      (node (ref "RV2") (pin "A") (pinfunction "A_A") (pintype "passive"))
      (node (ref "S-AMP") (pin "9") (pinfunction "IN-_9") (pintype "input"))
    )
    (net (code "62") (name "Net-(S-AMPD-IN+)") (class "Default")
      (node (ref "NTC") (pin "1") (pinfunction "1_1") (pintype "bidirectional"))
      (node (ref "R30") (pin "2") (pinfunction "2_2") (pintype "passive"))
      (node (ref "S-AMP") (pin "12") (pinfunction "IN+_12") (pintype "input"))
    )
    (net (code "63") (name "VDD") (class "Default")
      (node (ref "5V") (pin "1") (pinfunction "1_1") (pintype "bidirectional"))
      (node (ref "BRIGHTNESS") (pin "A") (pinfunction "A_A") (pintype "passive"))
      (node (ref "C1") (pin "1") (pinfunction "1_1") (pintype "passive"))
      (node (ref "C12") (pin "1") (pinfunction "+_1") (pintype "passive"))
      (node (ref "C14") (pin "2") (pinfunction "2_2") (pintype "passive"))
      (node (ref "C23") (pin "2") (pinfunction "2_2") (pintype "passive"))
      (node (ref "CONTRAST") (pin "A") (pinfunction "A_A") (pintype "passive"))
      (node (ref "D1") (pin "A") (pinfunction "A_A") (pintype "passive"))
      (node (ref "D6") (pin "A") (pinfunction "A_A") (pintype "passive"))
      (node (ref "IC1") (pin "20") (pinfunction "VDD_20") (pintype "power_in"))
      (node (ref "ICSP") (pin "2") (pinfunction "2_2") (pintype "passive"))
      (node (ref "JP1") (pin "1") (pinfunction "1_1") (pintype "passive"))
      (node (ref "L1") (pin "2") (pinfunction "2_2") (pintype "passive"))
      (node (ref "LCD_HEADER") (pin "2") (pinfunction "2_2") (pintype "passive"))
      (node (ref "R11") (pin "1") (pinfunction "1_1") (pintype "passive"))
      (node (ref "R13") (pin "1") (pinfunction "1_1") (pintype "passive"))
      (node (ref "R17") (pin "1") (pinfunction "1_1") (pintype "passive"))
      (node (ref "R19") (pin "1") (pinfunction "1_1") (pintype "passive"))
      (node (ref "R2") (pin "1") (pinfunction "1_1") (pintype "passive"))
      (node (ref "R20") (pin "1") (pinfunction "1_1") (pintype "passive"))
      (node (ref "R21") (pin "2") (pinfunction "2_2") (pintype "passive"))
      (node (ref "R29") (pin "2") (pinfunction "2_2") (pintype "passive"))
      (node (ref "R3") (pin "1") (pinfunction "1_1") (pintype "passive"))
      (node (ref "R30") (pin "1") (pinfunction "1_1") (pintype "passive"))
      (node (ref "R31") (pin "2") (pinfunction "2_2") (pintype "passive"))
      (node (ref "S-AMP") (pin "4") (pinfunction "V+_4") (pintype "power_in"))
      (node (ref "UART") (pin "4") (pinfunction "4_4") (pintype "passive"))
    )
    (net (code "64") (name "unconnected-(BRIGHTNESS-PadE)") (class "Default")
      (node (ref "BRIGHTNESS") (pin "E") (pinfunction "E_E") (pintype "passive"))
    )
    (net (code "65") (name "unconnected-(CAL-PadE)") (class "Default")
      (node (ref "CAL") (pin "E") (pinfunction "E_E") (pintype "passive"))
    )
    (net (code "66") (name "unconnected-(RV2-PadE)") (class "Default")
      (node (ref "RV2") (pin "E") (pinfunction "E_E") (pintype "passive"))
    )
    (net (code "67") (name "unconnected-(USB-GND-PadGND@1)") (class "Default")
      (node (ref "USB") (pin "GND@1") (pinfunction "GND_GND@1") (pintype "bidirectional"))
    )
    (net (code "68") (name "unconnected-(USB-GND-PadGND@2)") (class "Default")
      (node (ref "USB") (pin "GND@2") (pinfunction "GND_GND@2") (pintype "bidirectional"))
    )
  )
)
